# X15-Conversion.net
KiCad netlist of a schematic drawn in EAGLE
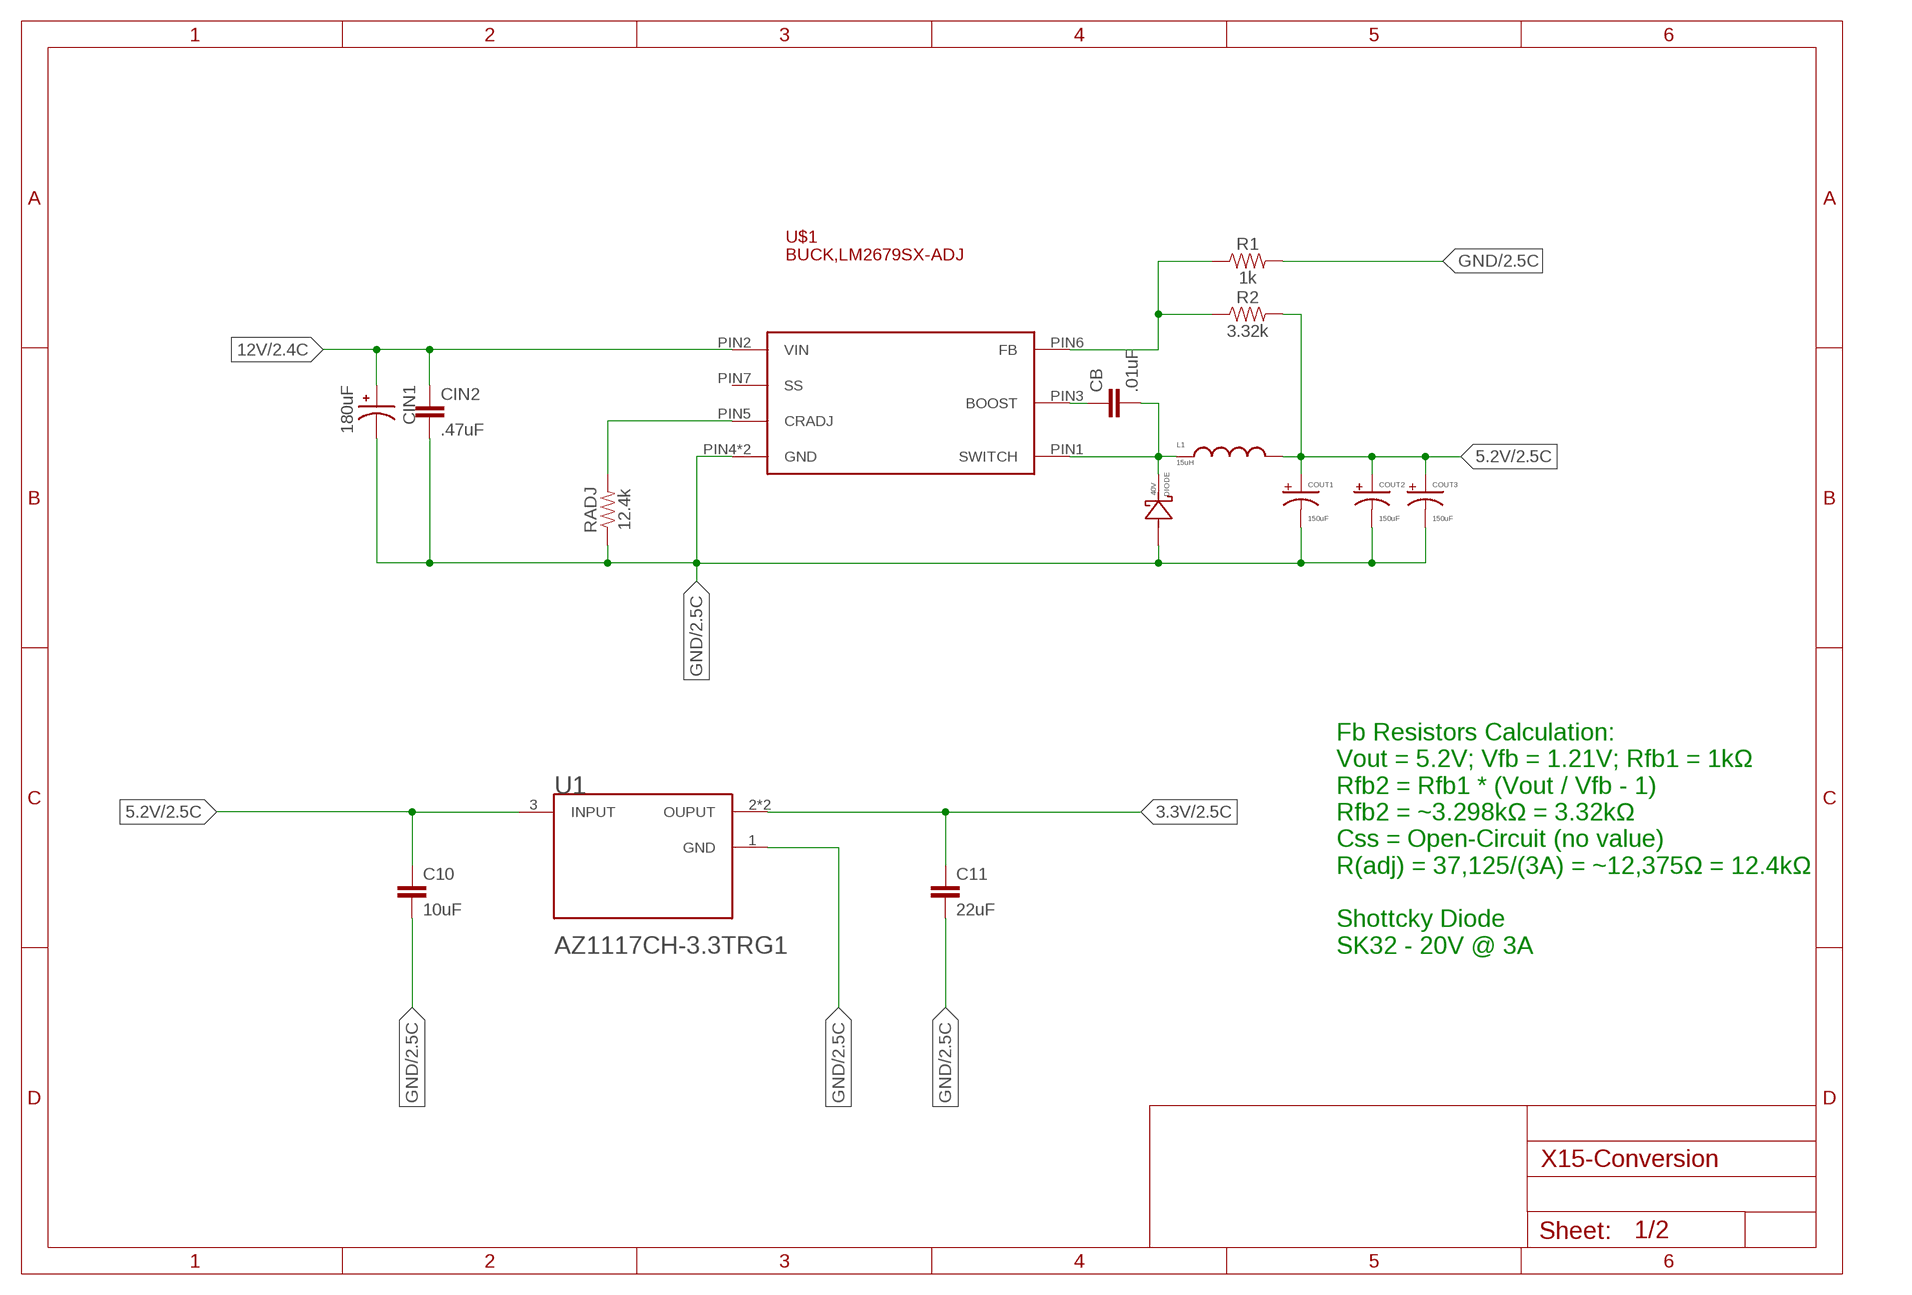
[diagram p0: schematic, sheet 1]
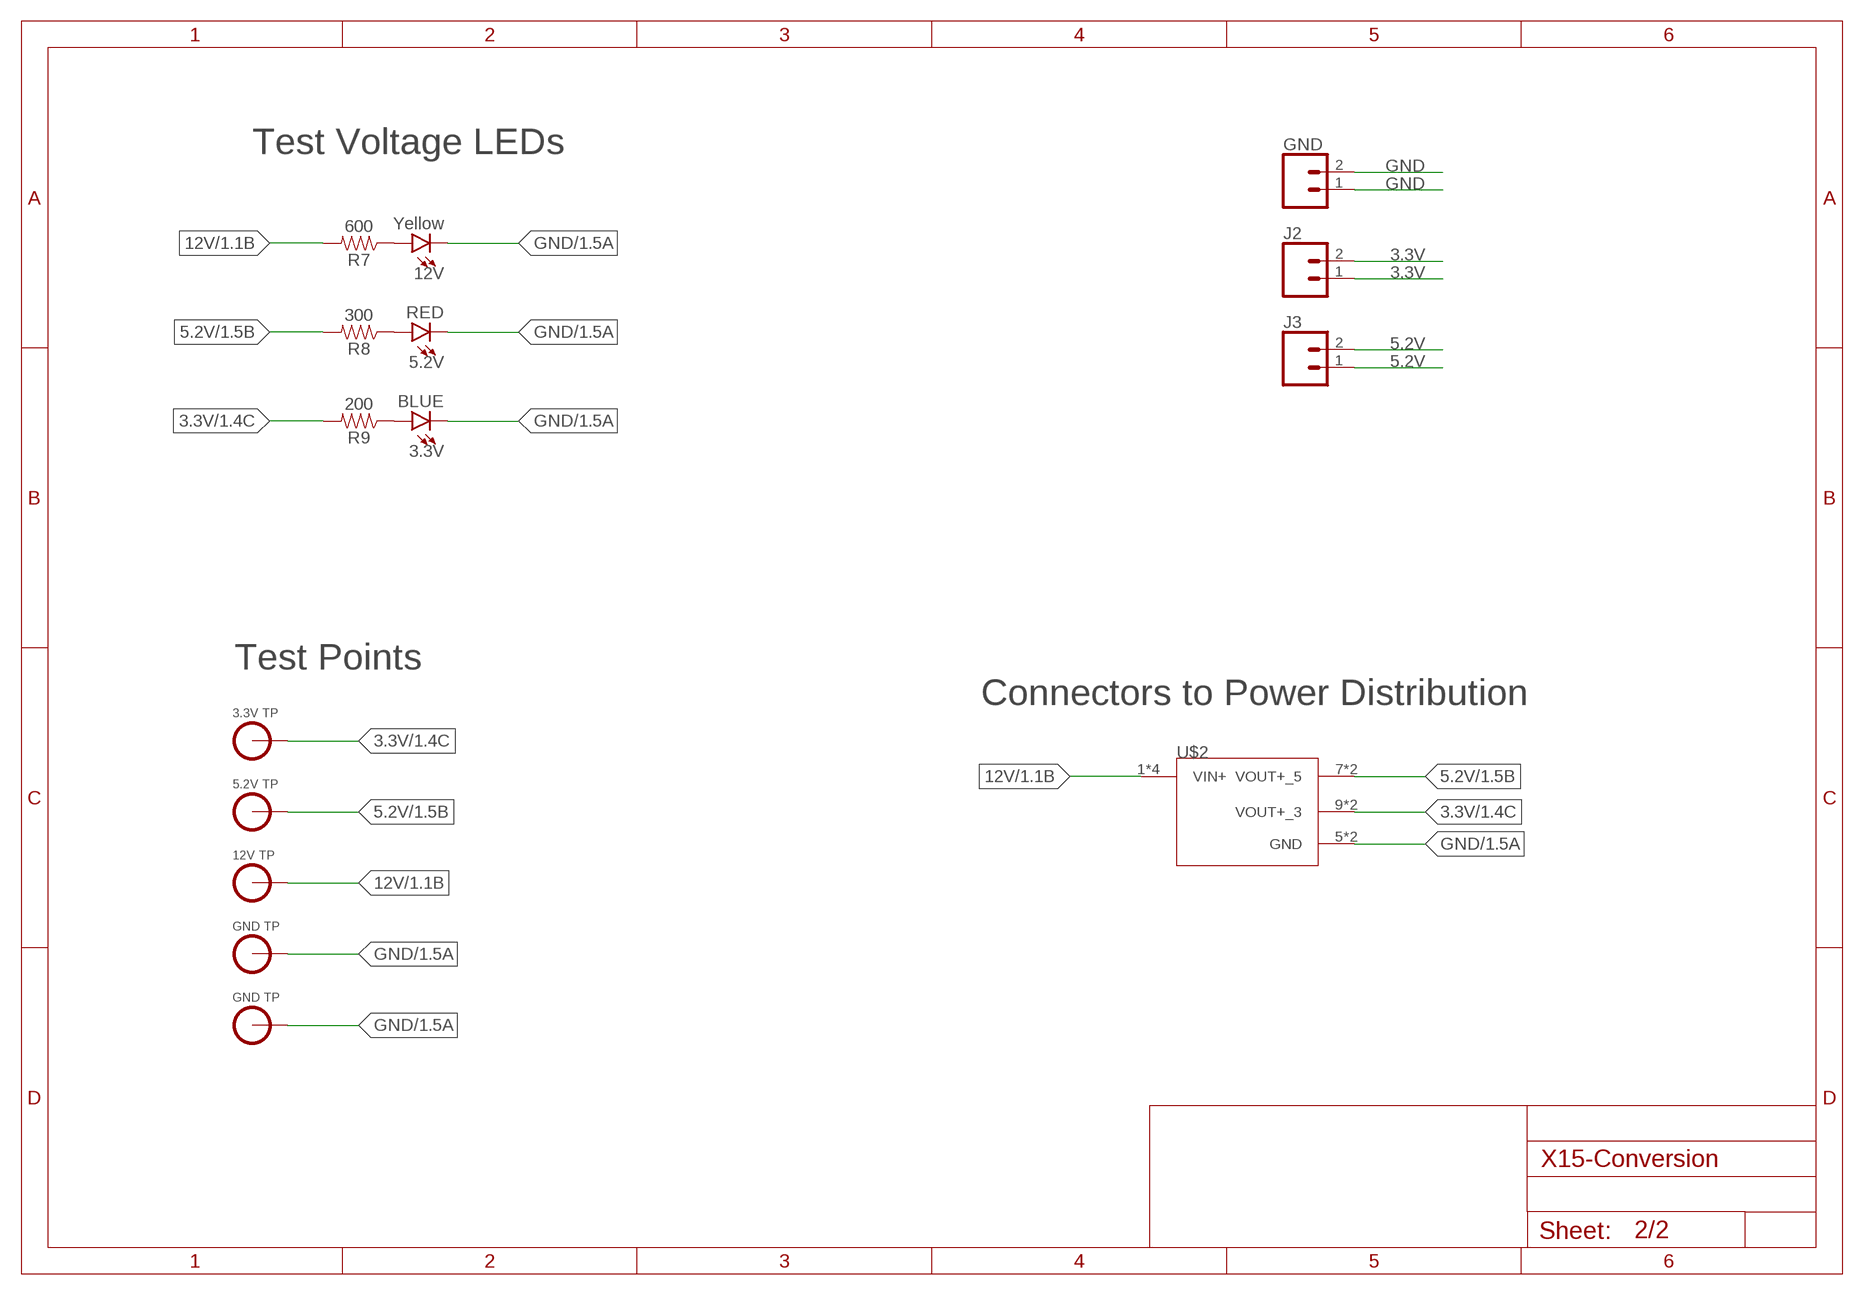
[diagram p1: schematic, sheet 2]

(export (version "E")
  (design (tool "Eeschema 10.0.6"))
  (components
    (comp (ref "C10")
      (value "10uF")
      (footprint "eagle-import:0603")
      (libsource (lib "eagle-import") (part "4.7PF-0603-50V-5%"))
    )
    (comp (ref "C11")
      (value "22uF")
      (footprint "eagle-import:0603")
      (libsource (lib "eagle-import") (part "4.7PF-0603-50V-5%"))
    )
    (comp (ref "CB")
      (value ".01uF")
      (footprint "eagle-import:0603")
      (libsource (lib "eagle-import") (part "4.7PF-0603-50V-5%"))
    )
    (comp (ref "CIN1")
      (value "180uF")
      (footprint "eagle-import:CAP_EEEFKE181XSP")
      (fields
        (field (name "DIGI-KEY_PART_NUMBER") "P18956TR-ND")
        (field (name "MF") "Panasonic")
        (field (name "MP") "EEEFKE181XSP")
      )
      (libsource (lib "eagle-import") (part "EEEFKE181XSP"))
    )
    (comp (ref "CIN2")
      (value ".47uF")
      (footprint "eagle-import:0603")
      (libsource (lib "eagle-import") (part "4.7PF-0603-50V-5%"))
    )
    (comp (ref "COUT1")
      (value "150uF")
      (footprint "eagle-import:2917(7343-31-METRIC)")
      (libsource (lib "eagle-import") (part "C-TANTALUM(10UF_150UF)"))
    )
    (comp (ref "COUT2")
      (value "150uF")
      (footprint "eagle-import:2917(7343-31-METRIC)")
      (libsource (lib "eagle-import") (part "C-TANTALUM(10UF_150UF)"))
    )
    (comp (ref "COUT3")
      (value "150uF")
      (footprint "eagle-import:2917(7343-31-METRIC)")
      (libsource (lib "eagle-import") (part "C-TANTALUM(10UF_150UF)"))
    )
    (comp (ref "DIODE")
      (value "40V")
      (footprint "eagle-import:DO214AC")
      (libsource (lib "eagle-import") (part "CDBG520-G"))
    )
    (comp (ref "L1")
      (value "15uH")
      (footprint "eagle-import:HCMA1305")
      (libsource (lib "eagle-import") (part "HCMA1305"))
    )
    (comp (ref "R1")
      (value "1k")
      (footprint "eagle-import:0603")
      (libsource (lib "eagle-import") (part "2.0KOHM-0603-1/10W-5%"))
    )
    (comp (ref "R2")
      (value "3.32k")
      (footprint "eagle-import:0603")
      (libsource (lib "eagle-import") (part "2.0KOHM-0603-1/10W-5%"))
    )
    (comp (ref "RADJ")
      (value "12.4k")
      (footprint "eagle-import:0603")
      (libsource (lib "eagle-import") (part "2.0KOHM-0603-1/10W-5%"))
    )
    (comp (ref "U$1")
      (value "BUCK,LM2679SX-ADJ")
      (footprint "eagle-import:BUCK,LM2679SX-ADJ")
      (libsource (lib "eagle-import") (part "BUCK,LM2679SX-ADJ"))
    )
    (comp (ref "U1")
      (value "LINEAR,AZ1117CR-3.3TRG1DIODES_AZ1117CH-3.3TRG1_0_0")
      (footprint "eagle-import:LINEAR,AZ1117CR-3.3TRG1")
      (fields (field (name "MF") "Diodes Inc.") (field (name "MP") "AZ1117CH-3.3TRG1"))
      (libsource (lib "eagle-import") (part "LINEAR,AZ1117CR-3.3TRG1DIODES_AZ1117CH-3.3TRG1_0_0"))
    )
    (comp (ref "3.3V")
      (value "BLUE")
      (footprint "eagle-import:LED-0603")
      (libsource (lib "eagle-import") (part "LED-BLUE0603"))
    )
    (comp (ref "5.2V")
      (value "RED")
      (footprint "eagle-import:LED-0603")
      (libsource (lib "eagle-import") (part "LED-RED0603"))
    )
    (comp (ref "12V")
      (value "Yellow")
      (footprint "eagle-import:LED-0603")
      (libsource (lib "eagle-import") (part "LED-YELLOW0603"))
    )
    (comp (ref "GND")
      (value "CONN_02")
      (footprint "eagle-import:1X02")
      (libsource (lib "eagle-import") (part "CONN_02"))
    )
    (comp (ref "J2")
      (value "CONN_02")
      (footprint "eagle-import:1X02")
      (libsource (lib "eagle-import") (part "CONN_02"))
    )
    (comp (ref "J3")
      (value "CONN_02")
      (footprint "eagle-import:1X02")
      (libsource (lib "eagle-import") (part "CONN_02"))
    )
    (comp (ref "R7")
      (value "600")
      (footprint "eagle-import:0603")
      (libsource (lib "eagle-import") (part "20OHM-0603-1/10W-1%"))
    )
    (comp (ref "R8")
      (value "300")
      (footprint "eagle-import:0603")
      (libsource (lib "eagle-import") (part "20OHM-0603-1/10W-1%"))
    )
    (comp (ref "R9")
      (value "200")
      (footprint "eagle-import:0603")
      (libsource (lib "eagle-import") (part "20OHM-0603-1/10W-1%"))
    )
    (comp (ref "U$2")
      (value "CONVERSION-DISTRIBUTION")
      (footprint "eagle-import:TSW-105-05-G-S(C-D)")
      (libsource (lib "eagle-import") (part "CONVERSION-DISTRIBUTION"))
    )
    (comp (ref "U$8")
      (value "3.3V_TESTPOINT")
      (footprint "eagle-import:3.3V_TESTPOINT")
      (libsource (lib "eagle-import") (part "3.3V_TESTPOINT"))
    )
    (comp (ref "U$9")
      (value "5.2V_TESTPOINT")
      (footprint "eagle-import:5.2V_TESTPOINT")
      (libsource (lib "eagle-import") (part "5.2V_TESTPOINT"))
    )
    (comp (ref "U$10")
      (value "12V_TESTPOINT")
      (footprint "eagle-import:12V_TESTPOINT")
      (libsource (lib "eagle-import") (part "12V_TESTPOINT"))
    )
    (comp (ref "U$11")
      (value "GND_TESTPOINT")
      (footprint "eagle-import:GND_TESTPOINT")
      (libsource (lib "eagle-import") (part "GND_TESTPOINT"))
    )
    (comp (ref "U$12")
      (value "GND_TESTPOINT")
      (footprint "eagle-import:GND_TESTPOINT")
      (libsource (lib "eagle-import") (part "GND_TESTPOINT"))
    )
  )
  (nets
    (net (code "1") (name "3.3V") (class "Default")
      (node (ref "C11") (pin "1") (pinfunction "1_1") (pintype "passive"))
      (node (ref "J2") (pin "1") (pinfunction "1_1") (pintype "passive"))
      (node (ref "J2") (pin "2") (pinfunction "2_2") (pintype "passive"))
      (node (ref "R9") (pin "2") (pinfunction "2_2") (pintype "passive"))
      (node (ref "U$2") (pin "10") (pinfunction "VOUT+_3_10") (pintype "bidirectional"))
      (node (ref "U$2") (pin "9") (pinfunction "VOUT+_3_9") (pintype "bidirectional"))
      (node (ref "U$8") (pin "3.3V") (pinfunction "3.3V_3.3V") (pintype "bidirectional"))
      (node (ref "U1") (pin "2") (pinfunction "OUPUT_2") (pintype "output"))
      (node (ref "U1") (pin "4") (pinfunction "OUPUT_4") (pintype "output"))
    )
    (net (code "2") (name "5.2V") (class "Default")
      (node (ref "C10") (pin "1") (pinfunction "1_1") (pintype "passive"))
      (node (ref "COUT1") (pin "+") (pinfunction "+_+") (pintype "passive"))
      (node (ref "COUT2") (pin "+") (pinfunction "+_+") (pintype "passive"))
      (node (ref "COUT3") (pin "+") (pinfunction "+_+") (pintype "passive"))
      (node (ref "J3") (pin "1") (pinfunction "1_1") (pintype "passive"))
      (node (ref "J3") (pin "2") (pinfunction "2_2") (pintype "passive"))
      (node (ref "L1") (pin "2") (pinfunction "2_2") (pintype "passive"))
      (node (ref "R2") (pin "2") (pinfunction "2_2") (pintype "passive"))
      (node (ref "R8") (pin "2") (pinfunction "2_2") (pintype "passive"))
      (node (ref "U$2") (pin "7") (pinfunction "VOUT+_5_7") (pintype "bidirectional"))
      (node (ref "U$2") (pin "8") (pinfunction "VOUT+_5_8") (pintype "bidirectional"))
      (node (ref "U$9") (pin "5.2V") (pinfunction "5.2V_5.2V") (pintype "bidirectional"))
      (node (ref "U1") (pin "3") (pinfunction "INPUT_3") (pintype "input"))
    )
    (net (code "3") (name "12V") (class "Default")
      (node (ref "CIN1") (pin "1") (pinfunction "1_1") (pintype "passive"))
      (node (ref "CIN2") (pin "1") (pinfunction "1_1") (pintype "passive"))
      (node (ref "R7") (pin "2") (pinfunction "2_2") (pintype "passive"))
      (node (ref "U$1") (pin "PIN2") (pinfunction "VIN_PIN2") (pintype "bidirectional"))
      (node (ref "U$10") (pin "12V") (pinfunction "12V_12V") (pintype "bidirectional"))
      (node (ref "U$2") (pin "1") (pinfunction "VIN+_1") (pintype "bidirectional"))
      (node (ref "U$2") (pin "2") (pinfunction "VIN+_2") (pintype "bidirectional"))
      (node (ref "U$2") (pin "3") (pinfunction "VIN+_3") (pintype "bidirectional"))
      (node (ref "U$2") (pin "4") (pinfunction "VIN+_4") (pintype "bidirectional"))
    )
    (net (code "4") (name "GND") (class "Default")
      (node (ref "12V") (pin "C") (pinfunction "C_C") (pintype "passive"))
      (node (ref "3.3V") (pin "C") (pinfunction "C_C") (pintype "passive"))
      (node (ref "5.2V") (pin "C") (pinfunction "C_C") (pintype "passive"))
      (node (ref "C10") (pin "2") (pinfunction "2_2") (pintype "passive"))
      (node (ref "C11") (pin "2") (pinfunction "2_2") (pintype "passive"))
      (node (ref "CIN1") (pin "2") (pinfunction "2_2") (pintype "passive"))
      (node (ref "CIN2") (pin "2") (pinfunction "2_2") (pintype "passive"))
      (node (ref "COUT1") (pin "-") (pinfunction "-_-") (pintype "passive"))
      (node (ref "COUT2") (pin "-") (pinfunction "-_-") (pintype "passive"))
      (node (ref "COUT3") (pin "-") (pinfunction "-_-") (pintype "passive"))
      (node (ref "DIODE") (pin "A") (pinfunction "2_A") (pintype "passive"))
      (node (ref "GND") (pin "1") (pinfunction "1_1") (pintype "passive"))
      (node (ref "GND") (pin "2") (pinfunction "2_2") (pintype "passive"))
      (node (ref "R1") (pin "2") (pinfunction "2_2") (pintype "passive"))
      (node (ref "RADJ") (pin "1") (pinfunction "1_1") (pintype "passive"))
      (node (ref "U$1") (pin "PIN4") (pinfunction "GND_PIN4") (pintype "bidirectional"))
      (node (ref "U$1") (pin "PIN8") (pinfunction "GND_PIN8") (pintype "bidirectional"))
      (node (ref "U$11") (pin "GND") (pinfunction "GND_GND") (pintype "bidirectional"))
      (node (ref "U$12") (pin "GND") (pinfunction "GND_GND") (pintype "bidirectional"))
      (node (ref "U$2") (pin "5") (pinfunction "GND_5") (pintype "bidirectional"))
      (node (ref "U$2") (pin "6") (pinfunction "GND_6") (pintype "bidirectional"))
      (node (ref "U1") (pin "1") (pinfunction "GND_1") (pintype "input"))
    )
    (net (code "5") (name "Net-(3.3V-PadA)") (class "Default")
      (node (ref "3.3V") (pin "A") (pinfunction "A_A") (pintype "passive"))
      (node (ref "R9") (pin "1") (pinfunction "1_1") (pintype "passive"))
    )
    (net (code "6") (name "Net-(5.2V-PadA)") (class "Default")
      (node (ref "5.2V") (pin "A") (pinfunction "A_A") (pintype "passive"))
      (node (ref "R8") (pin "1") (pinfunction "1_1") (pintype "passive"))
    )
    (net (code "7") (name "Net-(12V-PadA)") (class "Default")
      (node (ref "12V") (pin "A") (pinfunction "A_A") (pintype "passive"))
      (node (ref "R7") (pin "1") (pinfunction "1_1") (pintype "passive"))
    )
    (net (code "8") (name "Net-(DIODE-1)") (class "Default")
      (node (ref "CB") (pin "2") (pinfunction "2_2") (pintype "passive"))
      (node (ref "DIODE") (pin "C") (pinfunction "1_C") (pintype "passive"))
      (node (ref "L1") (pin "1") (pinfunction "1_1") (pintype "passive"))
      (node (ref "U$1") (pin "PIN1") (pinfunction "SWITCH_PIN1") (pintype "bidirectional"))
    )
    (net (code "9") (name "Net-(U$1-BOOST)") (class "Default")
      (node (ref "CB") (pin "1") (pinfunction "1_1") (pintype "passive"))
      (node (ref "U$1") (pin "PIN3") (pinfunction "BOOST_PIN3") (pintype "bidirectional"))
    )
    (net (code "10") (name "Net-(U$1-CRADJ)") (class "Default")
      (node (ref "RADJ") (pin "2") (pinfunction "2_2") (pintype "passive"))
      (node (ref "U$1") (pin "PIN5") (pinfunction "CRADJ_PIN5") (pintype "bidirectional"))
    )
    (net (code "11") (name "Net-(U$1-FB)") (class "Default")
      (node (ref "R1") (pin "1") (pinfunction "1_1") (pintype "passive"))
      (node (ref "R2") (pin "1") (pinfunction "1_1") (pintype "passive"))
      (node (ref "U$1") (pin "PIN6") (pinfunction "FB_PIN6") (pintype "bidirectional"))
    )
    (net (code "12") (name "unconnected-(U$1-SS-PadPIN7)") (class "Default")
      (node (ref "U$1") (pin "PIN7") (pinfunction "SS_PIN7") (pintype "bidirectional"))
    )
  )
)
